# PCB-TLY-LAMP.net
KiCad netlist of a schematic drawn in EAGLE
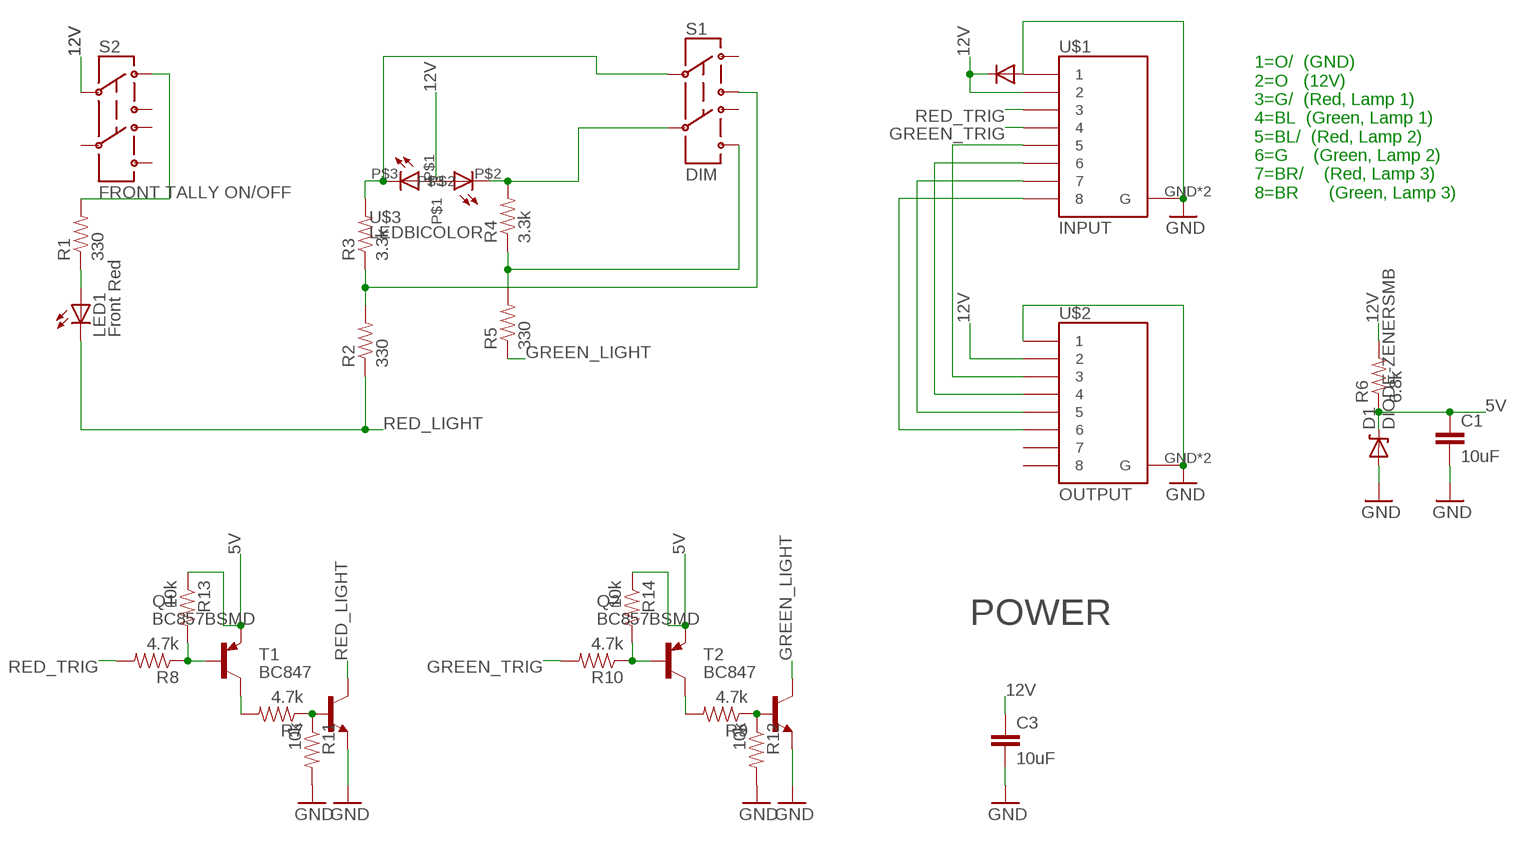
[diagram p0: schematic, sheet 1]

(export (version "E")
  (design (tool "Eeschema 10.0.6"))
  (components
    (comp (ref "C1")
      (value "10uF")
      (footprint "eagle-import:0805")
      (libsource (lib "eagle-import") (part "CAP0805"))
    )
    (comp (ref "C3")
      (value "10uF")
      (footprint "eagle-import:0805")
      (libsource (lib "eagle-import") (part "CAP0805"))
    )
    (comp (ref "D1")
      (value "DIODE-ZENERSMB")
      (footprint "eagle-import:SMB-DIODE")
      (libsource (lib "eagle-import") (part "DIODE-ZENERSMB"))
    )
    (comp (ref "LED1")
      (value "Front Red")
      (footprint "eagle-import:LED20")
      (libsource (lib "eagle-import") (part "LED20"))
    )
    (comp (ref "Q1")
      (value "BC857BSMD")
      (footprint "eagle-import:SOT23-BEC")
      (libsource (lib "eagle-import") (part "BC857SMDB"))
    )
    (comp (ref "Q2")
      (value "BC857BSMD")
      (footprint "eagle-import:SOT23-BEC")
      (libsource (lib "eagle-import") (part "BC857SMDB"))
    )
    (comp (ref "R1")
      (value "330")
      (footprint "eagle-import:0603-RES")
      (libsource (lib "eagle-import") (part "RESISTOR0603-RES"))
    )
    (comp (ref "R2")
      (value "330")
      (footprint "eagle-import:0603-RES")
      (libsource (lib "eagle-import") (part "RESISTOR0603-RES"))
    )
    (comp (ref "R3")
      (value "3.3k")
      (footprint "eagle-import:0603-RES")
      (libsource (lib "eagle-import") (part "RESISTOR0603-RES"))
    )
    (comp (ref "R4")
      (value "3.3k")
      (footprint "eagle-import:0603-RES")
      (libsource (lib "eagle-import") (part "RESISTOR0603-RES"))
    )
    (comp (ref "R5")
      (value "330")
      (footprint "eagle-import:0603-RES")
      (libsource (lib "eagle-import") (part "RESISTOR0603-RES"))
    )
    (comp (ref "R6")
      (value "6.8k")
      (footprint "eagle-import:0603-RES")
      (libsource (lib "eagle-import") (part "RESISTOR0603-RES"))
    )
    (comp (ref "R7")
      (value "4.7k")
      (footprint "eagle-import:0603-RES")
      (libsource (lib "eagle-import") (part "RESISTOR0603-RES"))
    )
    (comp (ref "R8")
      (value "4.7k")
      (footprint "eagle-import:0603-RES")
      (libsource (lib "eagle-import") (part "RESISTOR0603-RES"))
    )
    (comp (ref "R9")
      (value "4.7k")
      (footprint "eagle-import:0603-RES")
      (libsource (lib "eagle-import") (part "RESISTOR0603-RES"))
    )
    (comp (ref "R10")
      (value "4.7k")
      (footprint "eagle-import:0603-RES")
      (libsource (lib "eagle-import") (part "RESISTOR0603-RES"))
    )
    (comp (ref "R11")
      (value "10k")
      (footprint "eagle-import:0603-RES")
      (libsource (lib "eagle-import") (part "RESISTOR0603-RES"))
    )
    (comp (ref "R12")
      (value "10k")
      (footprint "eagle-import:0603-RES")
      (libsource (lib "eagle-import") (part "RESISTOR0603-RES"))
    )
    (comp (ref "R13")
      (value "10k")
      (footprint "eagle-import:0603-RES")
      (libsource (lib "eagle-import") (part "RESISTOR0603-RES"))
    )
    (comp (ref "R14")
      (value "10k")
      (footprint "eagle-import:0603-RES")
      (libsource (lib "eagle-import") (part "RESISTOR0603-RES"))
    )
    (comp (ref "S1")
      (value "DIM")
      (footprint "eagle-import:TECONNECTIVITY-DPDT")
      (libsource (lib "eagle-import") (part "SWITCH-DPDTPTH1"))
    )
    (comp (ref "S2")
      (value "FRONT TALLY ON/OFF")
      (footprint "eagle-import:TECONNECTIVITY-DPDT")
      (libsource (lib "eagle-import") (part "SWITCH-DPDTPTH1"))
    )
    (comp (ref "T1")
      (value "BC847")
      (footprint "eagle-import:SOT23")
      (libsource (lib "eagle-import") (part "BC847"))
    )
    (comp (ref "T2")
      (value "BC847")
      (footprint "eagle-import:SOT23")
      (libsource (lib "eagle-import") (part "BC847"))
    )
    (comp (ref "U$1")
      (value "INPUT")
      (footprint "eagle-import:RJ45-8_GND")
      (libsource (lib "eagle-import") (part "RJ45-8_GND"))
    )
    (comp (ref "U$2")
      (value "OUTPUT")
      (footprint "eagle-import:RJ45-8_GND")
      (libsource (lib "eagle-import") (part "RJ45-8_GND"))
    )
    (comp (ref "U$3")
      (value "LEDBICOLOR")
      (footprint "eagle-import:LEDBICOLOR")
      (libsource (lib "eagle-import") (part "LEDBICOLOR"))
    )
  )
  (nets
    (net (code "1") (name "/5V") (class "Default")
      (node (ref "C1") (pin "1") (pinfunction "1_1") (pintype "passive"))
      (node (ref "D1") (pin "C") (pinfunction "C_C") (pintype "passive"))
      (node (ref "Q1") (pin "E") (pinfunction "E_E") (pintype "passive"))
      (node (ref "Q2") (pin "E") (pinfunction "E_E") (pintype "passive"))
      (node (ref "R13") (pin "1") (pinfunction "1_1") (pintype "passive"))
      (node (ref "R14") (pin "1") (pinfunction "1_1") (pintype "passive"))
      (node (ref "R6") (pin "1") (pinfunction "1_1") (pintype "passive"))
    )
    (net (code "2") (name "/12V") (class "Default")
      (node (ref "C3") (pin "1") (pinfunction "1_1") (pintype "passive"))
      (node (ref "R6") (pin "2") (pinfunction "2_2") (pintype "passive"))
      (node (ref "S2") (pin "P$2") (pinfunction "2_P$2") (pintype "bidirectional"))
      (node (ref "U$1") (pin "2") (pinfunction "2_2") (pintype "bidirectional"))
      (node (ref "U$2") (pin "2") (pinfunction "2_2") (pintype "bidirectional"))
      (node (ref "U$3") (pin "P$1") (pinfunction "P$1_P$1") (pintype "bidirectional"))
    )
    (net (code "3") (name "/GREEN_LIGHT") (class "Default")
      (node (ref "R5") (pin "1") (pinfunction "1_1") (pintype "passive"))
      (node (ref "T2") (pin "3") (pinfunction "C_3") (pintype "passive"))
    )
    (net (code "4") (name "/GREEN_TRIG") (class "Default")
      (node (ref "R10") (pin "2") (pinfunction "2_2") (pintype "passive"))
      (node (ref "U$1") (pin "4") (pinfunction "4_4") (pintype "bidirectional"))
    )
    (net (code "5") (name "/RED_LIGHT") (class "Default")
      (node (ref "LED1") (pin "P$2") (pinfunction "C_P$2") (pintype "passive"))
      (node (ref "R2") (pin "1") (pinfunction "1_1") (pintype "passive"))
      (node (ref "T1") (pin "3") (pinfunction "C_3") (pintype "passive"))
    )
    (net (code "6") (name "/RED_TRIG") (class "Default")
      (node (ref "R8") (pin "2") (pinfunction "2_2") (pintype "passive"))
      (node (ref "U$1") (pin "3") (pinfunction "3_3") (pintype "bidirectional"))
    )
    (net (code "7") (name "GND") (class "Default")
      (node (ref "C1") (pin "2") (pinfunction "2_2") (pintype "passive"))
      (node (ref "C3") (pin "2") (pinfunction "2_2") (pintype "passive"))
      (node (ref "D1") (pin "A") (pinfunction "A_A") (pintype "passive"))
      (node (ref "R11") (pin "2") (pinfunction "2_2") (pintype "passive"))
      (node (ref "R12") (pin "2") (pinfunction "2_2") (pintype "passive"))
      (node (ref "T1") (pin "2") (pinfunction "E_2") (pintype "passive"))
      (node (ref "T2") (pin "2") (pinfunction "E_2") (pintype "passive"))
      (node (ref "U$1") (pin "1") (pinfunction "1_1") (pintype "bidirectional"))
      (node (ref "U$1") (pin "GND") (pinfunction "G_GND") (pintype "power_in"))
      (node (ref "U$1") (pin "GND1") (pinfunction "G_GND1") (pintype "power_in"))
      (node (ref "U$2") (pin "1") (pinfunction "1_1") (pintype "bidirectional"))
      (node (ref "U$2") (pin "GND") (pinfunction "G_GND") (pintype "power_in"))
      (node (ref "U$2") (pin "GND1") (pinfunction "G_GND1") (pintype "power_in"))
    )
    (net (code "8") (name "Net-(LED1-A)") (class "Default")
      (node (ref "LED1") (pin "P$1") (pinfunction "A_P$1") (pintype "passive"))
      (node (ref "R1") (pin "1") (pinfunction "1_1") (pintype "passive"))
    )
    (net (code "9") (name "Net-(Q1-PadB)") (class "Default")
      (node (ref "Q1") (pin "B") (pinfunction "B_B") (pintype "passive"))
      (node (ref "R13") (pin "2") (pinfunction "2_2") (pintype "passive"))
      (node (ref "R8") (pin "1") (pinfunction "1_1") (pintype "passive"))
    )
    (net (code "10") (name "Net-(Q1-PadC)") (class "Default")
      (node (ref "Q1") (pin "C") (pinfunction "C_C") (pintype "passive"))
      (node (ref "R7") (pin "2") (pinfunction "2_2") (pintype "passive"))
    )
    (net (code "11") (name "Net-(Q2-PadB)") (class "Default")
      (node (ref "Q2") (pin "B") (pinfunction "B_B") (pintype "passive"))
      (node (ref "R10") (pin "1") (pinfunction "1_1") (pintype "passive"))
      (node (ref "R14") (pin "2") (pinfunction "2_2") (pintype "passive"))
    )
    (net (code "12") (name "Net-(Q2-PadC)") (class "Default")
      (node (ref "Q2") (pin "C") (pinfunction "C_C") (pintype "passive"))
      (node (ref "R9") (pin "2") (pinfunction "2_2") (pintype "passive"))
    )
    (net (code "13") (name "Net-(S1-2)") (class "Default")
      (node (ref "R3") (pin "2") (pinfunction "2_2") (pintype "passive"))
      (node (ref "S1") (pin "P$2") (pinfunction "2_P$2") (pintype "bidirectional"))
      (node (ref "U$3") (pin "P$3") (pinfunction "P$3_P$3") (pintype "bidirectional"))
    )
    (net (code "14") (name "Net-(S1-3)") (class "Default")
      (node (ref "R2") (pin "2") (pinfunction "2_2") (pintype "passive"))
      (node (ref "R3") (pin "1") (pinfunction "1_1") (pintype "passive"))
      (node (ref "S1") (pin "P$3") (pinfunction "3_P$3") (pintype "bidirectional"))
    )
    (net (code "15") (name "Net-(S1-5)") (class "Default")
      (node (ref "R4") (pin "2") (pinfunction "2_2") (pintype "passive"))
      (node (ref "S1") (pin "P$5") (pinfunction "5_P$5") (pintype "bidirectional"))
      (node (ref "U$3") (pin "P$2") (pinfunction "P$2_P$2") (pintype "bidirectional"))
    )
    (net (code "16") (name "Net-(S1-6)") (class "Default")
      (node (ref "R4") (pin "1") (pinfunction "1_1") (pintype "passive"))
      (node (ref "R5") (pin "2") (pinfunction "2_2") (pintype "passive"))
      (node (ref "S1") (pin "P$6") (pinfunction "6_P$6") (pintype "bidirectional"))
    )
    (net (code "17") (name "Net-(S2-1)") (class "Default")
      (node (ref "R1") (pin "2") (pinfunction "2_2") (pintype "passive"))
      (node (ref "S2") (pin "P$1") (pinfunction "1_P$1") (pintype "bidirectional"))
    )
    (net (code "18") (name "Net-(T1-B)") (class "Default")
      (node (ref "R11") (pin "1") (pinfunction "1_1") (pintype "passive"))
      (node (ref "R7") (pin "1") (pinfunction "1_1") (pintype "passive"))
      (node (ref "T1") (pin "1") (pinfunction "B_1") (pintype "passive"))
    )
    (net (code "19") (name "Net-(T2-B)") (class "Default")
      (node (ref "R12") (pin "1") (pinfunction "1_1") (pintype "passive"))
      (node (ref "R9") (pin "1") (pinfunction "1_1") (pintype "passive"))
      (node (ref "T2") (pin "1") (pinfunction "B_1") (pintype "passive"))
    )
    (net (code "20") (name "Net-(U$1-Pad5)") (class "Default")
      (node (ref "U$1") (pin "5") (pinfunction "5_5") (pintype "bidirectional"))
      (node (ref "U$2") (pin "3") (pinfunction "3_3") (pintype "bidirectional"))
    )
    (net (code "21") (name "Net-(U$1-Pad6)") (class "Default")
      (node (ref "U$1") (pin "6") (pinfunction "6_6") (pintype "bidirectional"))
      (node (ref "U$2") (pin "4") (pinfunction "4_4") (pintype "bidirectional"))
    )
    (net (code "22") (name "Net-(U$1-Pad7)") (class "Default")
      (node (ref "U$1") (pin "7") (pinfunction "7_7") (pintype "bidirectional"))
      (node (ref "U$2") (pin "5") (pinfunction "5_5") (pintype "bidirectional"))
    )
    (net (code "23") (name "Net-(U$1-Pad8)") (class "Default")
      (node (ref "U$1") (pin "8") (pinfunction "8_8") (pintype "bidirectional"))
      (node (ref "U$2") (pin "6") (pinfunction "6_6") (pintype "bidirectional"))
    )
    (net (code "24") (name "unconnected-(S1-1-PadP$1)") (class "Default")
      (node (ref "S1") (pin "P$1") (pinfunction "1_P$1") (pintype "bidirectional"))
    )
    (net (code "25") (name "unconnected-(S1-4-PadP$4)") (class "Default")
      (node (ref "S1") (pin "P$4") (pinfunction "4_P$4") (pintype "bidirectional"))
    )
    (net (code "26") (name "unconnected-(S2-3-PadP$3)") (class "Default")
      (node (ref "S2") (pin "P$3") (pinfunction "3_P$3") (pintype "bidirectional"))
    )
    (net (code "27") (name "unconnected-(S2-4-PadP$4)") (class "Default")
      (node (ref "S2") (pin "P$4") (pinfunction "4_P$4") (pintype "bidirectional"))
    )
    (net (code "28") (name "unconnected-(S2-5-PadP$5)") (class "Default")
      (node (ref "S2") (pin "P$5") (pinfunction "5_P$5") (pintype "bidirectional"))
    )
    (net (code "29") (name "unconnected-(S2-6-PadP$6)") (class "Default")
      (node (ref "S2") (pin "P$6") (pinfunction "6_P$6") (pintype "bidirectional"))
    )
    (net (code "30") (name "unconnected-(U$2-Pad7)") (class "Default")
      (node (ref "U$2") (pin "7") (pinfunction "7_7") (pintype "bidirectional"))
    )
    (net (code "31") (name "unconnected-(U$2-Pad8)") (class "Default")
      (node (ref "U$2") (pin "8") (pinfunction "8_8") (pintype "bidirectional"))
    )
  )
)
